# Astable_multivibrator_2021-06-05.net
KiCad netlist of a schematic drawn in EasyEDA
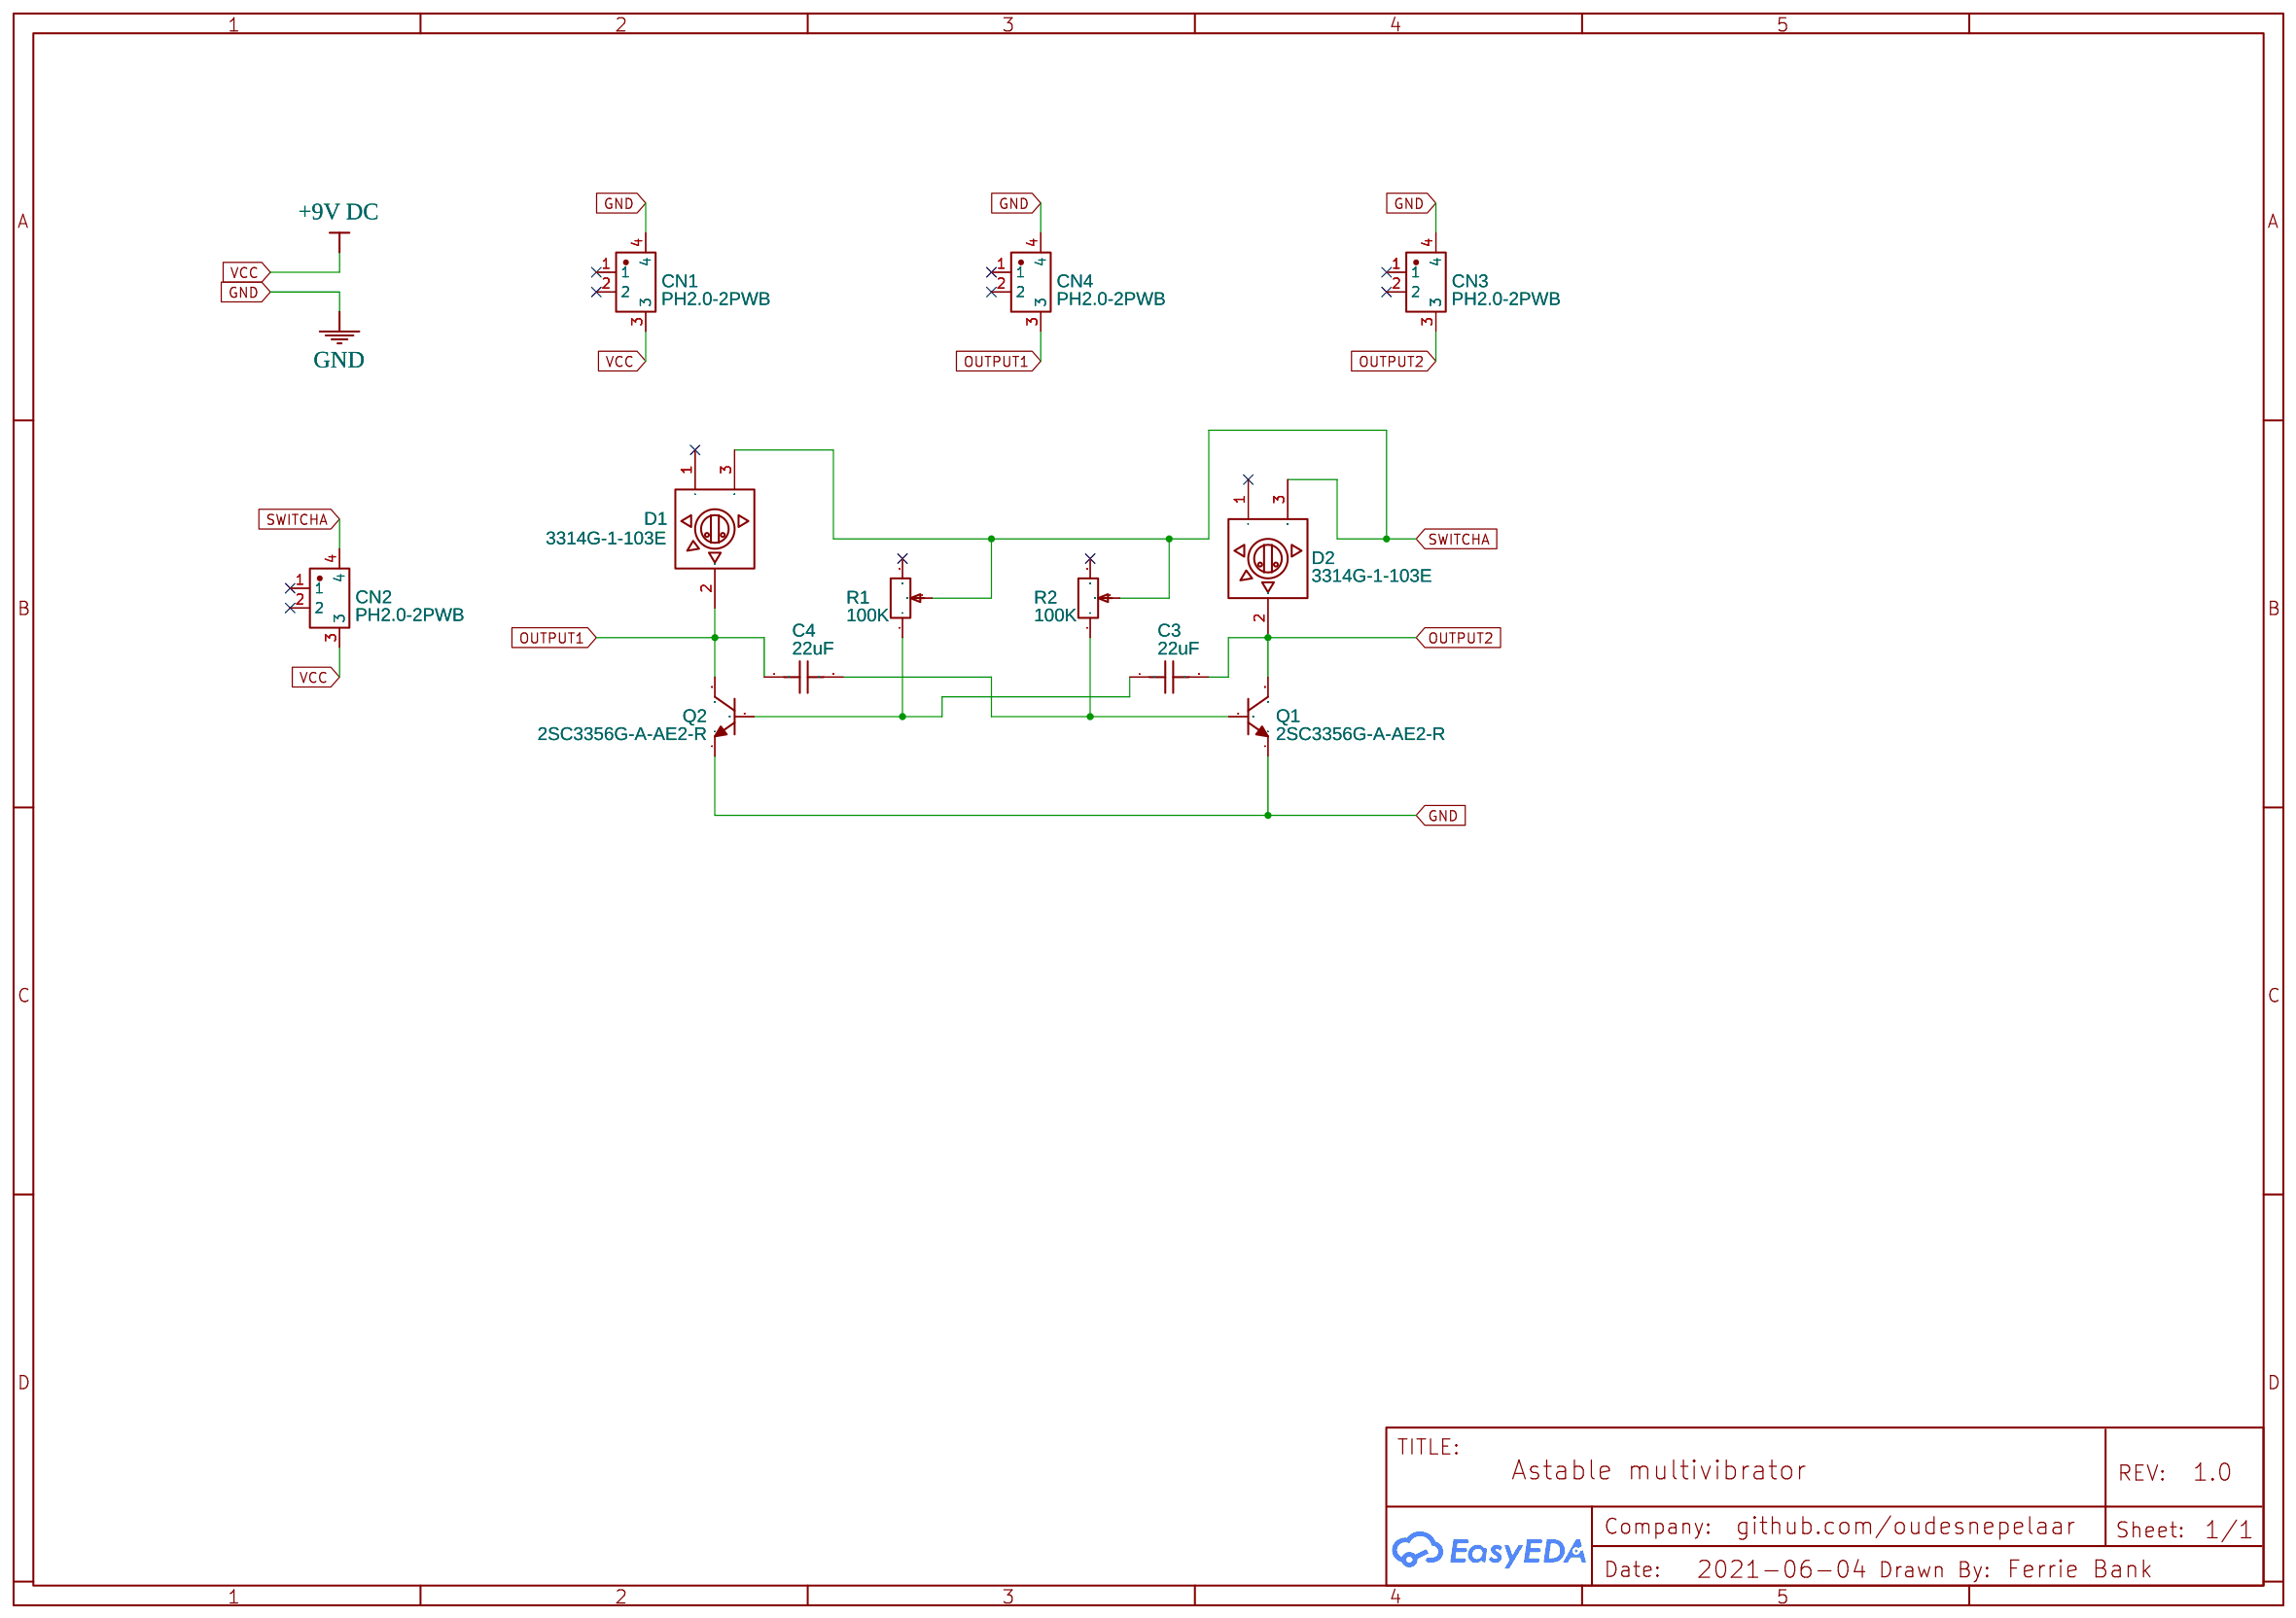
[diagram p0: schematic sheet]

(export (version "E")
  (design (tool "Eeschema 10.0.6"))
  (components
    (comp (ref "C3")
      (value "22uF")
      (fields
        (field (name "BOM_Manufacturer Part") "GRM21BC81C226ME44L")
        (field (name "BOM_Supplier Part") "C258782")
      )
      (libsource (lib "") (part "GRM21BC81C226ME44L"))
    )
    (comp (ref "C4")
      (value "22uF")
      (fields
        (field (name "BOM_Manufacturer Part") "GRM21BC81C226ME44L")
        (field (name "BOM_Supplier Part") "C258782")
      )
      (libsource (lib "") (part "GRM21BC81C226ME44L"))
    )
    (comp (ref "CN1")
      (value "PH2.0-2PWB")
      (fields
        (field (name "BOM_Manufacturer Part") "PH2.0-2PWB Horizontal")
        (field (name "BOM_Supplier Part") "C47647")
      )
      (libsource (lib "") (part "PH2.0-2PWB"))
    )
    (comp (ref "CN2")
      (value "PH2.0-2PWB")
      (fields
        (field (name "BOM_Manufacturer Part") "PH2.0-2PWB Horizontal")
        (field (name "BOM_Supplier Part") "C47647")
      )
      (libsource (lib "") (part "PH2.0-2PWB"))
    )
    (comp (ref "CN3")
      (value "PH2.0-2PWB")
      (fields
        (field (name "BOM_Manufacturer Part") "PH2.0-2PWB Horizontal")
        (field (name "BOM_Supplier Part") "C47647")
      )
      (libsource (lib "") (part "PH2.0-2PWB"))
    )
    (comp (ref "CN4")
      (value "PH2.0-2PWB")
      (fields
        (field (name "BOM_Manufacturer Part") "PH2.0-2PWB Horizontal")
        (field (name "BOM_Supplier Part") "C47647")
      )
      (libsource (lib "") (part "PH2.0-2PWB"))
    )
    (comp (ref "D1")
      (value "3314G-1-103E")
      (fields (field (name "BOM_Supplier Part") "C780220"))
      (libsource (lib "") (part "3314G-1-103E"))
    )
    (comp (ref "D2")
      (value "3314G-1-103E")
      (fields (field (name "BOM_Supplier Part") "C780220"))
      (libsource (lib "") (part "3314G-1-103E"))
    )
    (comp (ref "Q1")
      (value "2SC3356G-A-AE2-R")
      (fields (field (name "BOM_Supplier Part") "C171546"))
      (libsource (lib "") (part "2SC3356G-A-AE2-R_1"))
    )
    (comp (ref "Q2")
      (value "2SC3356G-A-AE2-R")
      (fields (field (name "BOM_Supplier Part") "C171546"))
      (libsource (lib "") (part "2SC3356G-A-AE2-R"))
    )
    (comp (ref "R1")
      (value "100K")
      (fields
        (field (name "BOM_Manufacturer Part") "3314J-1-104E")
        (field (name "BOM_Supplier Part") "C51284")
      )
      (libsource (lib "") (part "3314J-1-104E"))
    )
    (comp (ref "R2")
      (value "100K")
      (fields
        (field (name "BOM_Manufacturer Part") "3314J-1-104E")
        (field (name "BOM_Supplier Part") "C51284")
      )
      (libsource (lib "") (part "3314J-1-104E"))
    )
  )
  (nets
    (net (code "1") (name "GND") (class "Default")
      (node (ref "CN1") (pin "4") (pinfunction "4_4") (pintype "unspecified"))
      (node (ref "CN3") (pin "4") (pinfunction "4_4") (pintype "unspecified"))
      (node (ref "CN4") (pin "4") (pinfunction "4_4") (pintype "unspecified"))
      (node (ref "Q1") (pin "1") (pinfunction "E_1") (pintype "input"))
      (node (ref "Q2") (pin "1") (pinfunction "E_1") (pintype "input"))
    )
    (net (code "2") (name "Net-(Q1-B)") (class "Default")
      (node (ref "C4") (pin "2") (pinfunction "2_2") (pintype "unspecified"))
      (node (ref "Q1") (pin "2") (pinfunction "B_2") (pintype "input"))
      (node (ref "R2") (pin "1") (pinfunction "1_1") (pintype "input"))
    )
    (net (code "3") (name "Net-(Q2-B)") (class "Default")
      (node (ref "C3") (pin "1") (pinfunction "1_1") (pintype "unspecified"))
      (node (ref "Q2") (pin "2") (pinfunction "B_2") (pintype "input"))
      (node (ref "R1") (pin "1") (pinfunction "1_1") (pintype "input"))
    )
    (net (code "4") (name "OUTPUT1") (class "Default")
      (node (ref "C4") (pin "1") (pinfunction "1_1") (pintype "unspecified"))
      (node (ref "CN4") (pin "3") (pinfunction "3_3") (pintype "unspecified"))
      (node (ref "D1") (pin "2") (pinfunction "2_2") (pintype "unspecified"))
      (node (ref "Q2") (pin "3") (pinfunction "C_3") (pintype "input"))
    )
    (net (code "5") (name "OUTPUT2") (class "Default")
      (node (ref "C3") (pin "2") (pinfunction "2_2") (pintype "unspecified"))
      (node (ref "CN3") (pin "3") (pinfunction "3_3") (pintype "unspecified"))
      (node (ref "D2") (pin "2") (pinfunction "2_2") (pintype "unspecified"))
      (node (ref "Q1") (pin "3") (pinfunction "C_3") (pintype "input"))
    )
    (net (code "6") (name "SWITCHA") (class "Default")
      (node (ref "CN2") (pin "4") (pinfunction "4_4") (pintype "unspecified"))
      (node (ref "D1") (pin "3") (pinfunction "3_3") (pintype "unspecified"))
      (node (ref "D2") (pin "3") (pinfunction "3_3") (pintype "unspecified"))
      (node (ref "R1") (pin "2") (pinfunction "2_2") (pintype "input"))
      (node (ref "R2") (pin "2") (pinfunction "2_2") (pintype "input"))
    )
    (net (code "7") (name "VCC") (class "Default")
      (node (ref "CN1") (pin "3") (pinfunction "3_3") (pintype "unspecified"))
      (node (ref "CN2") (pin "3") (pinfunction "3_3") (pintype "unspecified"))
    )
    (net (code "8") (name "unconnected-(CN1-Pad1)") (class "Default")
      (node (ref "CN1") (pin "1") (pinfunction "1_1") (pintype "unspecified+no_connect"))
    )
    (net (code "9") (name "unconnected-(CN1-Pad2)") (class "Default")
      (node (ref "CN1") (pin "2") (pinfunction "2_2") (pintype "unspecified+no_connect"))
    )
    (net (code "10") (name "unconnected-(CN2-Pad1)") (class "Default")
      (node (ref "CN2") (pin "1") (pinfunction "1_1") (pintype "unspecified+no_connect"))
    )
    (net (code "11") (name "unconnected-(CN2-Pad2)") (class "Default")
      (node (ref "CN2") (pin "2") (pinfunction "2_2") (pintype "unspecified+no_connect"))
    )
    (net (code "12") (name "unconnected-(CN3-Pad1)") (class "Default")
      (node (ref "CN3") (pin "1") (pinfunction "1_1") (pintype "unspecified+no_connect"))
    )
    (net (code "13") (name "unconnected-(CN3-Pad2)") (class "Default")
      (node (ref "CN3") (pin "2") (pinfunction "2_2") (pintype "unspecified+no_connect"))
    )
    (net (code "14") (name "unconnected-(CN4-Pad1)") (class "Default")
      (node (ref "CN4") (pin "1") (pinfunction "1_1") (pintype "unspecified+no_connect"))
    )
    (net (code "15") (name "unconnected-(CN4-Pad2)") (class "Default")
      (node (ref "CN4") (pin "2") (pinfunction "2_2") (pintype "unspecified+no_connect"))
    )
    (net (code "16") (name "unconnected-(D1-Pad1)") (class "Default")
      (node (ref "D1") (pin "1") (pinfunction "1_1") (pintype "unspecified+no_connect"))
    )
    (net (code "17") (name "unconnected-(D2-Pad1)") (class "Default")
      (node (ref "D2") (pin "1") (pinfunction "1_1") (pintype "unspecified+no_connect"))
    )
    (net (code "18") (name "unconnected-(R1-Pad3)") (class "Default")
      (node (ref "R1") (pin "3") (pinfunction "3_3") (pintype "input+no_connect"))
    )
    (net (code "19") (name "unconnected-(R2-Pad3)") (class "Default")
      (node (ref "R2") (pin "3") (pinfunction "3_3") (pintype "input+no_connect"))
    )
  )
)
